# 07_FPGA_C.net
KiCad netlist of a schematic drawn in Altium Designer
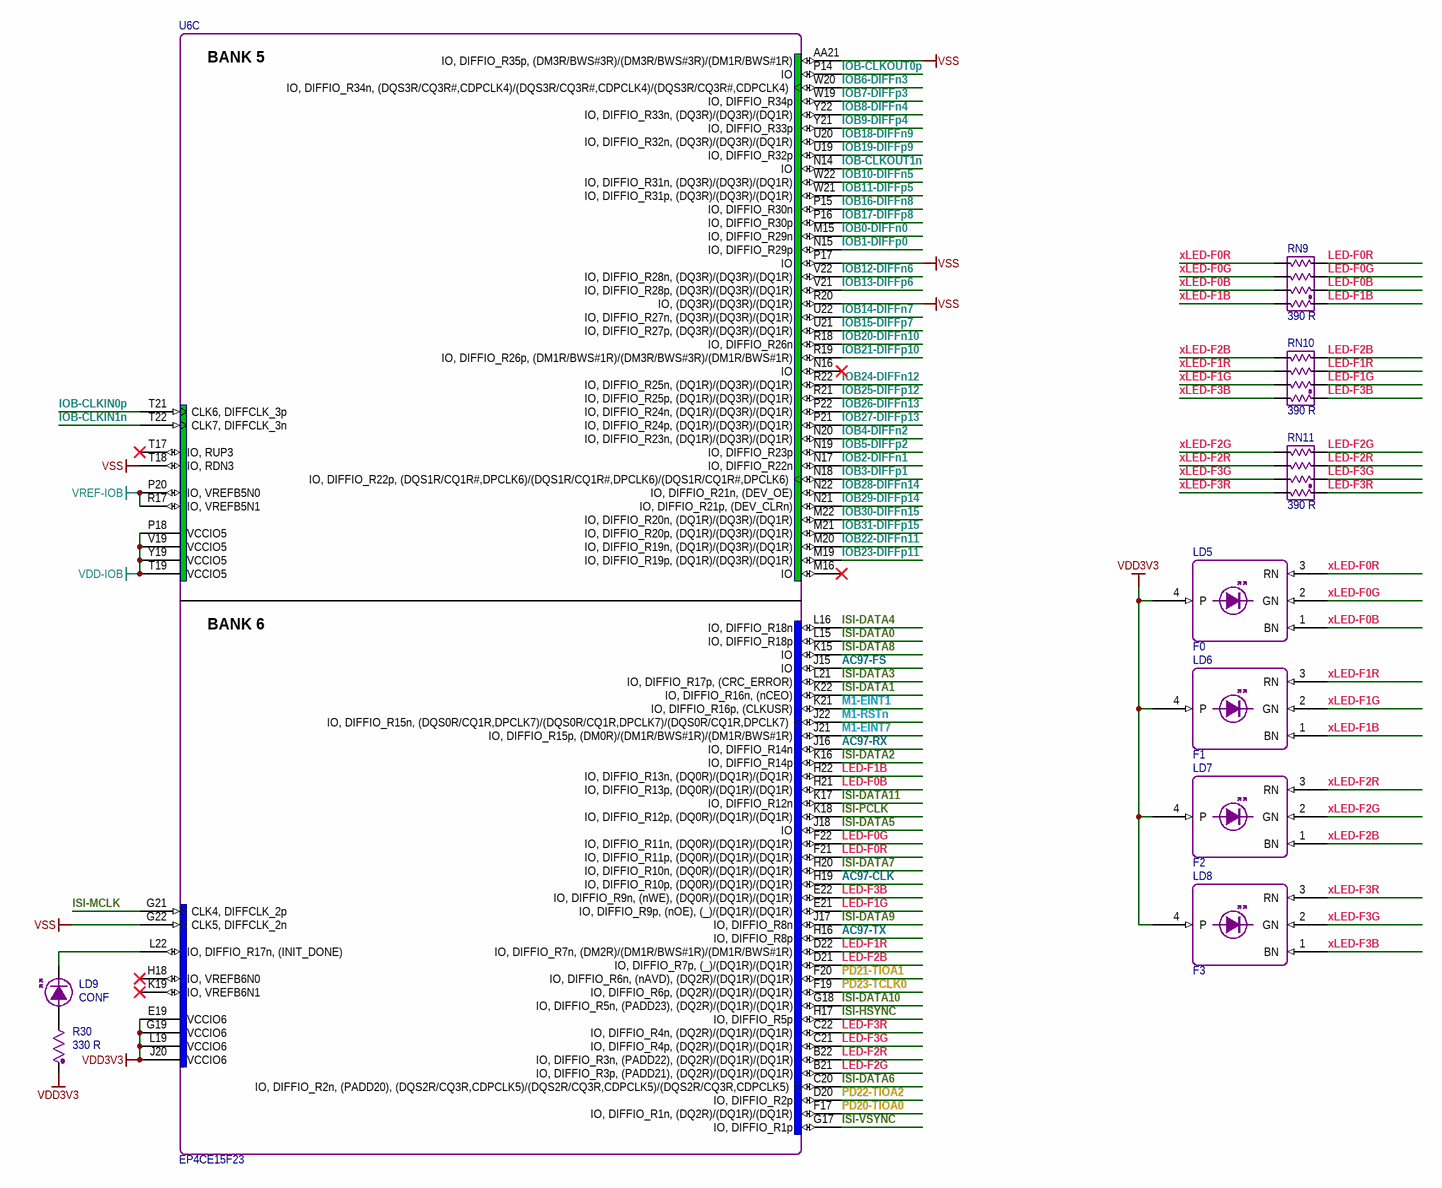
[diagram p0: 07_FPGA_C.SchDoc]

(export (version "E")
  (design (tool "Eeschema 10.0.6"))
  (components
    (comp (ref "LD5")
      (value "F0")
      (footprint "LED_4B_S_S197")
      (description "LED Pack 3")
      (fields
        (field (name "PARTNUMBER") "LL-S197BRGBC")
        (field (name "DESIGNER") "shyul")
        (field (name "PUBLISHER") "Cowin")
      )
      (libsource (lib "Basc_4_Other") (part "LED_3B"))
    )
    (comp (ref "LD6")
      (value "F1")
      (footprint "LED_4B_S_S197")
      (description "LED Pack 3")
      (fields
        (field (name "PARTNUMBER") "LL-S197BRGBC")
        (field (name "DESIGNER") "shyul")
        (field (name "PUBLISHER") "Cowin")
      )
      (libsource (lib "Basc_4_Other") (part "LED_3B"))
    )
    (comp (ref "LD7")
      (value "F2")
      (footprint "LED_4B_S_S197")
      (description "LED Pack 3")
      (fields
        (field (name "PARTNUMBER") "LL-S197BRGBC")
        (field (name "DESIGNER") "shyul")
        (field (name "PUBLISHER") "Cowin")
      )
      (libsource (lib "Basc_4_Other") (part "LED_3B"))
    )
    (comp (ref "LD8")
      (value "F3")
      (footprint "LED_4B_S_S197")
      (description "LED Pack 3")
      (fields
        (field (name "PARTNUMBER") "LL-S197BRGBC")
        (field (name "DESIGNER") "shyul")
        (field (name "PUBLISHER") "Cowin")
      )
      (libsource (lib "Basc_4_Other") (part "LED_3B"))
    )
    (comp (ref "LD9")
      (value "CONF")
      (footprint "0603LD")
      (description "LED Single")
      (fields
        (field (name "PARTNUMBER") "0")
        (field (name "DESIGNER") "shyul")
        (field (name "PUBLISHER") "Cowin")
      )
      (libsource (lib "Basc_4_Other") (part "LED"))
    )
    (comp (ref "R30")
      (value "330 R")
      (footprint "0402A2")
      (description "Normal Resistor")
      (fields
        (field (name "PARTNUMBER") "0")
        (field (name "DESIGNER") "shyul")
        (field (name "PUBLISHER") "Cowin")
      )
      (libsource (lib "Basc_1_Passive") (part "RES"))
    )
    (comp (ref "RN9")
      (value "390 R")
      (footprint "0402PR4")
      (description "Resistor Array x4")
      (fields
        (field (name "PARTNUMBER") "YC124-JR-07390RL")
        (field (name "PUBLISHER") "Cowin")
        (field (name "DESIGNER") "shyul")
      )
      (libsource (lib "Basc_1_Passive") (part "RES_N4"))
    )
    (comp (ref "RN10")
      (value "390 R")
      (footprint "0402PR4")
      (description "Resistor Array x4")
      (fields
        (field (name "PARTNUMBER") "YC124-JR-07390RL")
        (field (name "PUBLISHER") "Cowin")
        (field (name "DESIGNER") "shyul")
      )
      (libsource (lib "Basc_1_Passive") (part "RES_N4"))
    )
    (comp (ref "RN11")
      (value "390 R")
      (footprint "0402PR4")
      (description "Resistor Array x4")
      (fields
        (field (name "PARTNUMBER") "YC124-JR-07390RL")
        (field (name "PUBLISHER") "Cowin")
        (field (name "DESIGNER") "shyul")
      )
      (libsource (lib "Basc_1_Passive") (part "RES_N4"))
    )
    (comp (ref "U6")
      (value "EP4CE15F23")
      (footprint "FBGA-484")
      (description "Cyclone IV EP4CE15F23 FPGA")
      (fields
        (field (name "PARTNUMBER") "EP4CE15F23C8N")
        (field (name "DESIGNER") "shyul")
        (field (name "PUBLISHER") "Cowin")
      )
      (libsource (lib "PCB_XEM-S91") (part "EP4CE15F23"))
    )
  )
  (nets
    (net (code "1") (name "/AC97-CLK") (class "Default")
      (node (ref "U6") (pin "H19") (pinfunction "IO,_DIFFIO_R10p,_(DQ0R)/(DQ1R)/(DQ1R)_H19") (pintype "bidirectional"))
    )
    (net (code "2") (name "/AC97-FS") (class "Default")
      (node (ref "U6") (pin "J15") (pinfunction "IO_J15") (pintype "bidirectional"))
    )
    (net (code "3") (name "/AC97-RX") (class "Default")
      (node (ref "U6") (pin "J16") (pinfunction "IO,_DIFFIO_R14n_J16") (pintype "bidirectional"))
    )
    (net (code "4") (name "/AC97-TX") (class "Default")
      (node (ref "U6") (pin "H16") (pinfunction "IO,_DIFFIO_R8p_H16") (pintype "bidirectional"))
    )
    (net (code "5") (name "/IOB-CLKIN0p") (class "Default")
      (node (ref "U6") (pin "T21") (pinfunction "CLK6,_DIFFCLK_3p_T21") (pintype "input"))
    )
    (net (code "6") (name "/IOB-CLKIN1n") (class "Default")
      (node (ref "U6") (pin "T22") (pinfunction "CLK7,_DIFFCLK_3n_T22") (pintype "input"))
    )
    (net (code "7") (name "/IOB-CLKOUT0p") (class "Default")
      (node (ref "U6") (pin "P14") (pinfunction "IO_P14") (pintype "bidirectional"))
    )
    (net (code "8") (name "/IOB-CLKOUT1n") (class "Default")
      (node (ref "U6") (pin "N14") (pinfunction "IO_N14") (pintype "bidirectional"))
    )
    (net (code "9") (name "/IOB0-DIFFn0") (class "Default")
      (node (ref "U6") (pin "M15") (pinfunction "IO,_DIFFIO_R29n_M15") (pintype "bidirectional"))
    )
    (net (code "10") (name "/IOB1-DIFFp0") (class "Default")
      (node (ref "U6") (pin "N15") (pinfunction "IO,_DIFFIO_R29p_N15") (pintype "bidirectional"))
    )
    (net (code "11") (name "/IOB2-DIFFn1") (class "Default")
      (node (ref "U6") (pin "N17") (pinfunction "IO,_DIFFIO_R22n_N17") (pintype "bidirectional"))
    )
    (net (code "12") (name "/IOB3-DIFFp1") (class "Default")
      (node (ref "U6") (pin "N18") (pinfunction "IO,_DIFFIO_R22p,_(DQS1R/CQ1R#,DPCLK6)/(DQS1R/CQ1R#,DPCLK6)/(DQS1R/CQ1R#,DPCLK6)_N18") (pintype "bidirectional"))
    )
    (net (code "13") (name "/IOB4-DIFFn2") (class "Default")
      (node (ref "U6") (pin "N20") (pinfunction "IO,_DIFFIO_R23n,_(DQ1R)/(DQ3R)/(DQ1R)_N20") (pintype "bidirectional"))
    )
    (net (code "14") (name "/IOB5-DIFFp2") (class "Default")
      (node (ref "U6") (pin "N19") (pinfunction "IO,_DIFFIO_R23p_N19") (pintype "bidirectional"))
    )
    (net (code "15") (name "/IOB6-DIFFn3") (class "Default")
      (node (ref "U6") (pin "W20") (pinfunction "IO,_DIFFIO_R34n,_(DQS3R/CQ3R#,CDPCLK4)/(DQS3R/CQ3R#,CDPCLK4)/(DQS3R/CQ3R#,CDPCLK4)_W20") (pintype "bidirectional"))
    )
    (net (code "16") (name "/IOB7-DIFFp3") (class "Default")
      (node (ref "U6") (pin "W19") (pinfunction "IO,_DIFFIO_R34p_W19") (pintype "bidirectional"))
    )
    (net (code "17") (name "/IOB8-DIFFn4") (class "Default")
      (node (ref "U6") (pin "Y22") (pinfunction "IO,_DIFFIO_R33n,_(DQ3R)/(DQ3R)/(DQ1R)_Y22") (pintype "bidirectional"))
    )
    (net (code "18") (name "/IOB9-DIFFp4") (class "Default")
      (node (ref "U6") (pin "Y21") (pinfunction "IO,_DIFFIO_R33p_Y21") (pintype "bidirectional"))
    )
    (net (code "19") (name "/IOB10-DIFFn5") (class "Default")
      (node (ref "U6") (pin "W22") (pinfunction "IO,_DIFFIO_R31n,_(DQ3R)/(DQ3R)/(DQ1R)_W22") (pintype "bidirectional"))
    )
    (net (code "20") (name "/IOB11-DIFFp5") (class "Default")
      (node (ref "U6") (pin "W21") (pinfunction "IO,_DIFFIO_R31p,_(DQ3R)/(DQ3R)/(DQ1R)_W21") (pintype "bidirectional"))
    )
    (net (code "21") (name "/IOB12-DIFFn6") (class "Default")
      (node (ref "U6") (pin "V22") (pinfunction "IO,_DIFFIO_R28n,_(DQ3R)/(DQ3R)/(DQ1R)_V22") (pintype "bidirectional"))
    )
    (net (code "22") (name "/IOB13-DIFFp6") (class "Default")
      (node (ref "U6") (pin "V21") (pinfunction "IO,_DIFFIO_R28p,_(DQ3R)/(DQ3R)/(DQ1R)_V21") (pintype "bidirectional"))
    )
    (net (code "23") (name "/IOB14-DIFFn7") (class "Default")
      (node (ref "U6") (pin "U22") (pinfunction "IO,_DIFFIO_R27n,_(DQ3R)/(DQ3R)/(DQ1R)_U22") (pintype "bidirectional"))
    )
    (net (code "24") (name "/IOB15-DIFFp7") (class "Default")
      (node (ref "U6") (pin "U21") (pinfunction "IO,_DIFFIO_R27p,_(DQ3R)/(DQ3R)/(DQ1R)_U21") (pintype "bidirectional"))
    )
    (net (code "25") (name "/IOB16-DIFFn8") (class "Default")
      (node (ref "U6") (pin "P15") (pinfunction "IO,_DIFFIO_R30n_P15") (pintype "bidirectional"))
    )
    (net (code "26") (name "/IOB17-DIFFp8") (class "Default")
      (node (ref "U6") (pin "P16") (pinfunction "IO,_DIFFIO_R30p_P16") (pintype "bidirectional"))
    )
    (net (code "27") (name "/IOB18-DIFFn9") (class "Default")
      (node (ref "U6") (pin "U20") (pinfunction "IO,_DIFFIO_R32n,_(DQ3R)/(DQ3R)/(DQ1R)_U20") (pintype "bidirectional"))
    )
    (net (code "28") (name "/IOB19-DIFFp9") (class "Default")
      (node (ref "U6") (pin "U19") (pinfunction "IO,_DIFFIO_R32p_U19") (pintype "bidirectional"))
    )
    (net (code "29") (name "/IOB20-DIFFn10") (class "Default")
      (node (ref "U6") (pin "R18") (pinfunction "IO,_DIFFIO_R26n_R18") (pintype "bidirectional"))
    )
    (net (code "30") (name "/IOB21-DIFFp10") (class "Default")
      (node (ref "U6") (pin "R19") (pinfunction "IO,_DIFFIO_R26p,_(DM1R/BWS#1R)/(DM3R/BWS#3R)/(DM1R/BWS#1R)_R19") (pintype "bidirectional"))
    )
    (net (code "31") (name "/IOB22-DIFFn11") (class "Default")
      (node (ref "U6") (pin "M20") (pinfunction "IO,_DIFFIO_R19n,_(DQ1R)/(DQ3R)/(DQ1R)_M20") (pintype "bidirectional"))
    )
    (net (code "32") (name "/IOB23-DIFFp11") (class "Default")
      (node (ref "U6") (pin "M19") (pinfunction "IO,_DIFFIO_R19p,_(DQ1R)/(DQ3R)/(DQ1R)_M19") (pintype "bidirectional"))
    )
    (net (code "33") (name "/IOB24-DIFFn12") (class "Default")
      (node (ref "U6") (pin "R22") (pinfunction "IO,_DIFFIO_R25n,_(DQ1R)/(DQ3R)/(DQ1R)_R22") (pintype "bidirectional"))
    )
    (net (code "34") (name "/IOB25-DIFFp12") (class "Default")
      (node (ref "U6") (pin "R21") (pinfunction "IO,_DIFFIO_R25p,_(DQ1R)/(DQ3R)/(DQ1R)_R21") (pintype "bidirectional"))
    )
    (net (code "35") (name "/IOB26-DIFFn13") (class "Default")
      (node (ref "U6") (pin "P22") (pinfunction "IO,_DIFFIO_R24n,_(DQ1R)/(DQ3R)/(DQ1R)_P22") (pintype "bidirectional"))
    )
    (net (code "36") (name "/IOB27-DIFFp13") (class "Default")
      (node (ref "U6") (pin "P21") (pinfunction "IO,_DIFFIO_R24p,_(DQ1R)/(DQ3R)/(DQ1R)_P21") (pintype "bidirectional"))
    )
    (net (code "37") (name "/IOB28-DIFFn14") (class "Default")
      (node (ref "U6") (pin "N22") (pinfunction "IO,_DIFFIO_R21n,_(DEV_OE)_N22") (pintype "bidirectional"))
    )
    (net (code "38") (name "/IOB29-DIFFp14") (class "Default")
      (node (ref "U6") (pin "N21") (pinfunction "IO,_DIFFIO_R21p,_(DEV_CLRn)_N21") (pintype "bidirectional"))
    )
    (net (code "39") (name "/IOB30-DIFFn15") (class "Default")
      (node (ref "U6") (pin "M22") (pinfunction "IO,_DIFFIO_R20n,_(DQ1R)/(DQ3R)/(DQ1R)_M22") (pintype "bidirectional"))
    )
    (net (code "40") (name "/IOB31-DIFFp15") (class "Default")
      (node (ref "U6") (pin "M21") (pinfunction "IO,_DIFFIO_R20p,_(DQ1R)/(DQ3R)/(DQ1R)_M21") (pintype "bidirectional"))
    )
    (net (code "41") (name "/ISI-DATA0") (class "Default")
      (node (ref "U6") (pin "L15") (pinfunction "IO,_DIFFIO_R18p_L15") (pintype "bidirectional"))
    )
    (net (code "42") (name "/ISI-DATA1") (class "Default")
      (node (ref "U6") (pin "K22") (pinfunction "IO,_DIFFIO_R16n,_(nCEO)_K22") (pintype "bidirectional"))
    )
    (net (code "43") (name "/ISI-DATA2") (class "Default")
      (node (ref "U6") (pin "K16") (pinfunction "IO,_DIFFIO_R14p_K16") (pintype "bidirectional"))
    )
    (net (code "44") (name "/ISI-DATA3") (class "Default")
      (node (ref "U6") (pin "L21") (pinfunction "IO,_DIFFIO_R17p,_(CRC_ERROR)_L21") (pintype "bidirectional"))
    )
    (net (code "45") (name "/ISI-DATA4") (class "Default")
      (node (ref "U6") (pin "L16") (pinfunction "IO,_DIFFIO_R18n_L16") (pintype "bidirectional"))
    )
    (net (code "46") (name "/ISI-DATA5") (class "Default")
      (node (ref "U6") (pin "J18") (pinfunction "IO_J18") (pintype "bidirectional"))
    )
    (net (code "47") (name "/ISI-DATA6") (class "Default")
      (node (ref "U6") (pin "C20") (pinfunction "IO,_DIFFIO_R2n,_(PADD20),_(DQS2R/CQ3R,CDPCLK5)/(DQS2R/CQ3R,CDPCLK5)/(DQS2R/CQ3R,CDPCLK5)_C20") (pintype "bidirectional"))
    )
    (net (code "48") (name "/ISI-DATA7") (class "Default")
      (node (ref "U6") (pin "H20") (pinfunction "IO,_DIFFIO_R10n,_(DQ0R)/(DQ1R)/(DQ1R)_H20") (pintype "bidirectional"))
    )
    (net (code "49") (name "/ISI-DATA8") (class "Default")
      (node (ref "U6") (pin "K15") (pinfunction "IO_K15") (pintype "bidirectional"))
    )
    (net (code "50") (name "/ISI-DATA9") (class "Default")
      (node (ref "U6") (pin "J17") (pinfunction "IO,_DIFFIO_R8n_J17") (pintype "bidirectional"))
    )
    (net (code "51") (name "/ISI-DATA10") (class "Default")
      (node (ref "U6") (pin "G18") (pinfunction "IO,_DIFFIO_R5n,_(PADD23),_(DQ2R)/(DQ1R)/(DQ1R)_G18") (pintype "bidirectional"))
    )
    (net (code "52") (name "/ISI-DATA11") (class "Default")
      (node (ref "U6") (pin "K17") (pinfunction "IO,_DIFFIO_R12n_K17") (pintype "bidirectional"))
    )
    (net (code "53") (name "/ISI-HSYNC") (class "Default")
      (node (ref "U6") (pin "H17") (pinfunction "IO,_DIFFIO_R5p_H17") (pintype "bidirectional"))
    )
    (net (code "54") (name "/ISI-MCLK") (class "Default")
      (node (ref "U6") (pin "G21") (pinfunction "CLK4,_DIFFCLK_2p_G21") (pintype "input"))
    )
    (net (code "55") (name "/ISI-PCLK") (class "Default")
      (node (ref "U6") (pin "K18") (pinfunction "IO,_DIFFIO_R12p,_(DQ0R)/(DQ1R)/(DQ1R)_K18") (pintype "bidirectional"))
    )
    (net (code "56") (name "/ISI-VSYNC") (class "Default")
      (node (ref "U6") (pin "G17") (pinfunction "IO,_DIFFIO_R1p_G17") (pintype "bidirectional"))
    )
    (net (code "57") (name "/LED-F0B") (class "Default")
      (node (ref "RN9") (pin "3") (pinfunction "3_3") (pintype "passive"))
      (node (ref "U6") (pin "H21") (pinfunction "IO,_DIFFIO_R13p,_(DQ0R)/(DQ1R)/(DQ1R)_H21") (pintype "bidirectional"))
    )
    (net (code "58") (name "/LED-F0G") (class "Default")
      (node (ref "RN9") (pin "5") (pinfunction "5_5") (pintype "passive"))
      (node (ref "U6") (pin "F22") (pinfunction "IO,_DIFFIO_R11n,_(DQ0R)/(DQ1R)/(DQ1R)_F22") (pintype "bidirectional"))
    )
    (net (code "59") (name "/LED-F0R") (class "Default")
      (node (ref "RN9") (pin "7") (pinfunction "7_7") (pintype "passive"))
      (node (ref "U6") (pin "F21") (pinfunction "IO,_DIFFIO_R11p,_(DQ0R)/(DQ1R)/(DQ1R)_F21") (pintype "bidirectional"))
    )
    (net (code "60") (name "/LED-F1B") (class "Default")
      (node (ref "RN9") (pin "1") (pinfunction "1_1") (pintype "passive"))
      (node (ref "U6") (pin "H22") (pinfunction "IO,_DIFFIO_R13n,_(DQ0R)/(DQ1R)/(DQ1R)_H22") (pintype "bidirectional"))
    )
    (net (code "61") (name "/LED-F1G") (class "Default")
      (node (ref "RN10") (pin "3") (pinfunction "3_3") (pintype "passive"))
      (node (ref "U6") (pin "E21") (pinfunction "IO,_DIFFIO_R9p,_(nOE),_(_)/(DQ1R)/(DQ1R)_E21") (pintype "bidirectional"))
    )
    (net (code "62") (name "/LED-F1R") (class "Default")
      (node (ref "RN10") (pin "5") (pinfunction "5_5") (pintype "passive"))
      (node (ref "U6") (pin "D22") (pinfunction "IO,_DIFFIO_R7n,_(DM2R)/(DM1R/BWS#1R)/(DM1R/BWS#1R)_D22") (pintype "bidirectional"))
    )
    (net (code "63") (name "/LED-F2B") (class "Default")
      (node (ref "RN10") (pin "7") (pinfunction "7_7") (pintype "passive"))
      (node (ref "U6") (pin "D21") (pinfunction "IO,_DIFFIO_R7p,_(_)/(DQ1R)/(DQ1R)_D21") (pintype "bidirectional"))
    )
    (net (code "64") (name "/LED-F2G") (class "Default")
      (node (ref "RN11") (pin "7") (pinfunction "7_7") (pintype "passive"))
      (node (ref "U6") (pin "B21") (pinfunction "IO,_DIFFIO_R3p,_(PADD21),_(DQ2R)/(DQ1R)/(DQ1R)_B21") (pintype "bidirectional"))
    )
    (net (code "65") (name "/LED-F2R") (class "Default")
      (node (ref "RN11") (pin "5") (pinfunction "5_5") (pintype "passive"))
      (node (ref "U6") (pin "B22") (pinfunction "IO,_DIFFIO_R3n,_(PADD22),_(DQ2R)/(DQ1R)/(DQ1R)_B22") (pintype "bidirectional"))
    )
    (net (code "66") (name "/LED-F3B") (class "Default")
      (node (ref "RN10") (pin "1") (pinfunction "1_1") (pintype "passive"))
      (node (ref "U6") (pin "E22") (pinfunction "IO,_DIFFIO_R9n,_(nWE),_(DQ0R)/(DQ1R)/(DQ1R)_E22") (pintype "bidirectional"))
    )
    (net (code "67") (name "/LED-F3G") (class "Default")
      (node (ref "RN11") (pin "3") (pinfunction "3_3") (pintype "passive"))
      (node (ref "U6") (pin "C21") (pinfunction "IO,_DIFFIO_R4p,_(DQ2R)/(DQ1R)/(DQ1R)_C21") (pintype "bidirectional"))
    )
    (net (code "68") (name "/LED-F3R") (class "Default")
      (node (ref "RN11") (pin "1") (pinfunction "1_1") (pintype "passive"))
      (node (ref "U6") (pin "C22") (pinfunction "IO,_DIFFIO_R4n,_(DQ2R)/(DQ1R)/(DQ1R)_C22") (pintype "bidirectional"))
    )
    (net (code "69") (name "/M1-EINT1") (class "Default")
      (node (ref "U6") (pin "K21") (pinfunction "IO,_DIFFIO_R16p,_(CLKUSR)_K21") (pintype "bidirectional"))
    )
    (net (code "70") (name "/M1-EINT7") (class "Default")
      (node (ref "U6") (pin "J21") (pinfunction "IO,_DIFFIO_R15p,_(DM0R)/(DM1R/BWS#1R)/(DM1R/BWS#1R)_J21") (pintype "bidirectional"))
    )
    (net (code "71") (name "/M1-RSTn") (class "Default")
      (node (ref "U6") (pin "J22") (pinfunction "IO,_DIFFIO_R15n,_(DQS0R/CQ1R,DPCLK7)/(DQS0R/CQ1R,DPCLK7)/(DQS0R/CQ1R,DPCLK7)_J22") (pintype "bidirectional"))
    )
    (net (code "72") (name "/PD20-TIOA0") (class "Default")
      (node (ref "U6") (pin "F17") (pinfunction "IO,_DIFFIO_R1n,_(DQ2R)/(DQ1R)/(DQ1R)_F17") (pintype "bidirectional"))
    )
    (net (code "73") (name "/PD21-TIOA1") (class "Default")
      (node (ref "U6") (pin "F20") (pinfunction "IO,_DIFFIO_R6n,_(nAVD),_(DQ2R)/(DQ1R)/(DQ1R)_F20") (pintype "bidirectional"))
    )
    (net (code "74") (name "/PD22-TIOA2") (class "Default")
      (node (ref "U6") (pin "D20") (pinfunction "IO,_DIFFIO_R2p_D20") (pintype "bidirectional"))
    )
    (net (code "75") (name "/PD23-TCLK0") (class "Default")
      (node (ref "U6") (pin "F19") (pinfunction "IO,_DIFFIO_R6p,_(DQ2R)/(DQ1R)/(DQ1R)_F19") (pintype "bidirectional"))
    )
    (net (code "76") (name "/xLED-F0B") (class "Default")
      (node (ref "LD5") (pin "1") (pinfunction "BN_1") (pintype "input"))
      (node (ref "RN9") (pin "4") (pinfunction "4_4") (pintype "passive"))
    )
    (net (code "77") (name "/xLED-F0G") (class "Default")
      (node (ref "LD5") (pin "2") (pinfunction "GN_2") (pintype "input"))
      (node (ref "RN9") (pin "6") (pinfunction "6_6") (pintype "passive"))
    )
    (net (code "78") (name "/xLED-F0R") (class "Default")
      (node (ref "LD5") (pin "3") (pinfunction "RN_3") (pintype "input"))
      (node (ref "RN9") (pin "8") (pinfunction "8_8") (pintype "passive"))
    )
    (net (code "79") (name "/xLED-F1B") (class "Default")
      (node (ref "LD6") (pin "1") (pinfunction "BN_1") (pintype "input"))
      (node (ref "RN9") (pin "2") (pinfunction "2_2") (pintype "passive"))
    )
    (net (code "80") (name "/xLED-F1G") (class "Default")
      (node (ref "LD6") (pin "2") (pinfunction "GN_2") (pintype "input"))
      (node (ref "RN10") (pin "4") (pinfunction "4_4") (pintype "passive"))
    )
    (net (code "81") (name "/xLED-F1R") (class "Default")
      (node (ref "LD6") (pin "3") (pinfunction "RN_3") (pintype "input"))
      (node (ref "RN10") (pin "6") (pinfunction "6_6") (pintype "passive"))
    )
    (net (code "82") (name "/xLED-F2B") (class "Default")
      (node (ref "LD7") (pin "1") (pinfunction "BN_1") (pintype "input"))
      (node (ref "RN10") (pin "8") (pinfunction "8_8") (pintype "passive"))
    )
    (net (code "83") (name "/xLED-F2G") (class "Default")
      (node (ref "LD7") (pin "2") (pinfunction "GN_2") (pintype "input"))
      (node (ref "RN11") (pin "8") (pinfunction "8_8") (pintype "passive"))
    )
    (net (code "84") (name "/xLED-F2R") (class "Default")
      (node (ref "LD7") (pin "3") (pinfunction "RN_3") (pintype "input"))
      (node (ref "RN11") (pin "6") (pinfunction "6_6") (pintype "passive"))
    )
    (net (code "85") (name "/xLED-F3B") (class "Default")
      (node (ref "LD8") (pin "1") (pinfunction "BN_1") (pintype "input"))
      (node (ref "RN10") (pin "2") (pinfunction "2_2") (pintype "passive"))
    )
    (net (code "86") (name "/xLED-F3G") (class "Default")
      (node (ref "LD8") (pin "2") (pinfunction "GN_2") (pintype "input"))
      (node (ref "RN11") (pin "4") (pinfunction "4_4") (pintype "passive"))
    )
    (net (code "87") (name "/xLED-F3R") (class "Default")
      (node (ref "LD8") (pin "3") (pinfunction "RN_3") (pintype "input"))
      (node (ref "RN11") (pin "2") (pinfunction "2_2") (pintype "passive"))
    )
    (net (code "88") (name "Net-(LD9-Pad2)") (class "Default")
      (node (ref "LD9") (pin "2") (pinfunction "2_2") (pintype "passive"))
      (node (ref "R30") (pin "1") (pinfunction "1_1") (pintype "passive"))
    )
    (net (code "89") (name "Net-(U6C-IO,_DIFFIO_R17n,_(INIT_DONE))") (class "Default")
      (node (ref "LD9") (pin "1") (pinfunction "1_1") (pintype "passive"))
      (node (ref "U6") (pin "L22") (pinfunction "IO,_DIFFIO_R17n,_(INIT_DONE)_L22") (pintype "bidirectional"))
    )
    (net (code "90") (name "VDD-IOB") (class "Default")
      (node (ref "U6") (pin "P18") (pinfunction "VCCIO5_P18") (pintype "power_in"))
      (node (ref "U6") (pin "T19") (pinfunction "VCCIO5_T19") (pintype "power_in"))
      (node (ref "U6") (pin "V19") (pinfunction "VCCIO5_V19") (pintype "power_in"))
      (node (ref "U6") (pin "Y19") (pinfunction "VCCIO5_Y19") (pintype "power_in"))
    )
    (net (code "91") (name "VDD3V3") (class "Default")
      (node (ref "LD5") (pin "4") (pinfunction "P_4") (pintype "input"))
      (node (ref "LD6") (pin "4") (pinfunction "P_4") (pintype "input"))
      (node (ref "LD7") (pin "4") (pinfunction "P_4") (pintype "input"))
      (node (ref "LD8") (pin "4") (pinfunction "P_4") (pintype "input"))
      (node (ref "R30") (pin "2") (pinfunction "2_2") (pintype "passive"))
      (node (ref "U6") (pin "E19") (pinfunction "VCCIO6_E19") (pintype "power_in"))
      (node (ref "U6") (pin "G19") (pinfunction "VCCIO6_G19") (pintype "power_in"))
      (node (ref "U6") (pin "J20") (pinfunction "VCCIO6_J20") (pintype "power_in"))
      (node (ref "U6") (pin "L19") (pinfunction "VCCIO6_L19") (pintype "power_in"))
    )
    (net (code "92") (name "VREF-IOB") (class "Default")
      (node (ref "U6") (pin "P20") (pinfunction "IO,_VREFB5N0_P20") (pintype "bidirectional"))
      (node (ref "U6") (pin "R17") (pinfunction "IO,_VREFB5N1_R17") (pintype "bidirectional"))
    )
    (net (code "93") (name "VSS") (class "Default")
      (node (ref "U6") (pin "AA21") (pinfunction "IO,_DIFFIO_R35p,_(DM3R/BWS#3R)/(DM3R/BWS#3R)/(DM1R/BWS#1R)_AA21") (pintype "bidirectional"))
      (node (ref "U6") (pin "G22") (pinfunction "CLK5,_DIFFCLK_2n_G22") (pintype "input"))
      (node (ref "U6") (pin "P17") (pinfunction "IO_P17") (pintype "bidirectional"))
      (node (ref "U6") (pin "R20") (pinfunction "IO,_(DQ3R)/(DQ3R)/(DQ1R)_R20") (pintype "bidirectional"))
      (node (ref "U6") (pin "T18") (pinfunction "IO,_RDN3_T18") (pintype "bidirectional"))
    )
    (net (code "94") (name "unconnected-(U6C-IO,_RUP3-PadT17)") (class "Default")
      (node (ref "U6") (pin "T17") (pinfunction "IO,_RUP3_T17") (pintype "bidirectional+no_connect"))
    )
    (net (code "95") (name "unconnected-(U6C-IO,_VREFB6N0-PadH18)") (class "Default")
      (node (ref "U6") (pin "H18") (pinfunction "IO,_VREFB6N0_H18") (pintype "bidirectional+no_connect"))
    )
    (net (code "96") (name "unconnected-(U6C-IO,_VREFB6N1-PadK19)") (class "Default")
      (node (ref "U6") (pin "K19") (pinfunction "IO,_VREFB6N1_K19") (pintype "bidirectional+no_connect"))
    )
    (net (code "97") (name "unconnected-(U6C-IO-PadM16)") (class "Default")
      (node (ref "U6") (pin "M16") (pinfunction "IO_M16") (pintype "bidirectional+no_connect"))
    )
    (net (code "98") (name "unconnected-(U6C-IO-PadN16)") (class "Default")
      (node (ref "U6") (pin "N16") (pinfunction "IO_N16") (pintype "bidirectional+no_connect"))
    )
  )
)
